# Kaya.net
KiCad netlist of a schematic drawn in EAGLE
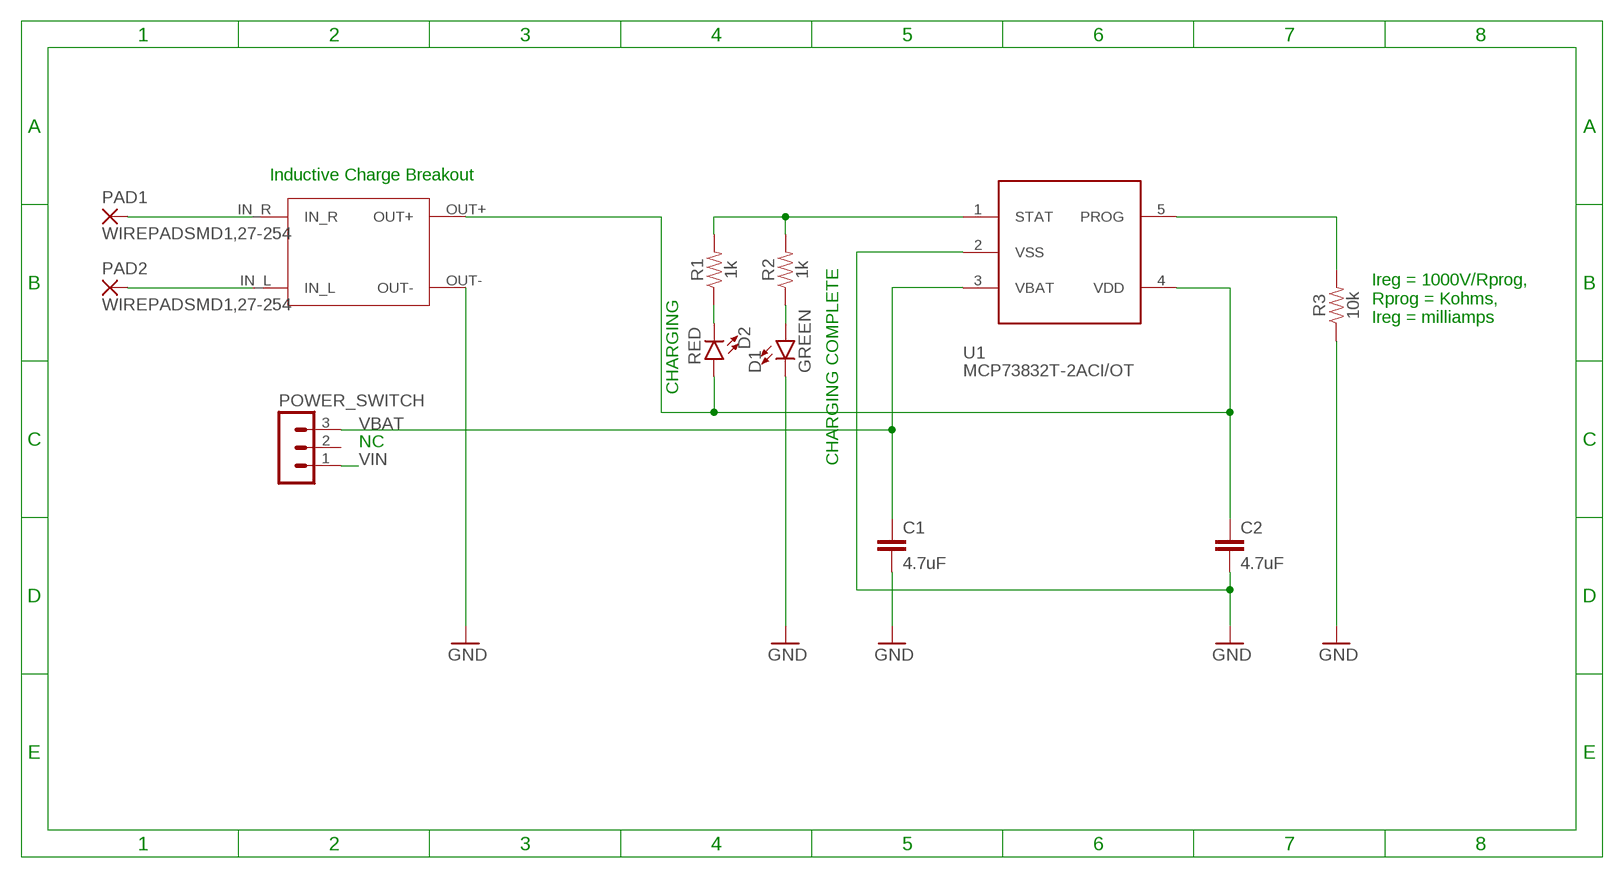
[diagram p0: schematic, sheet 1]
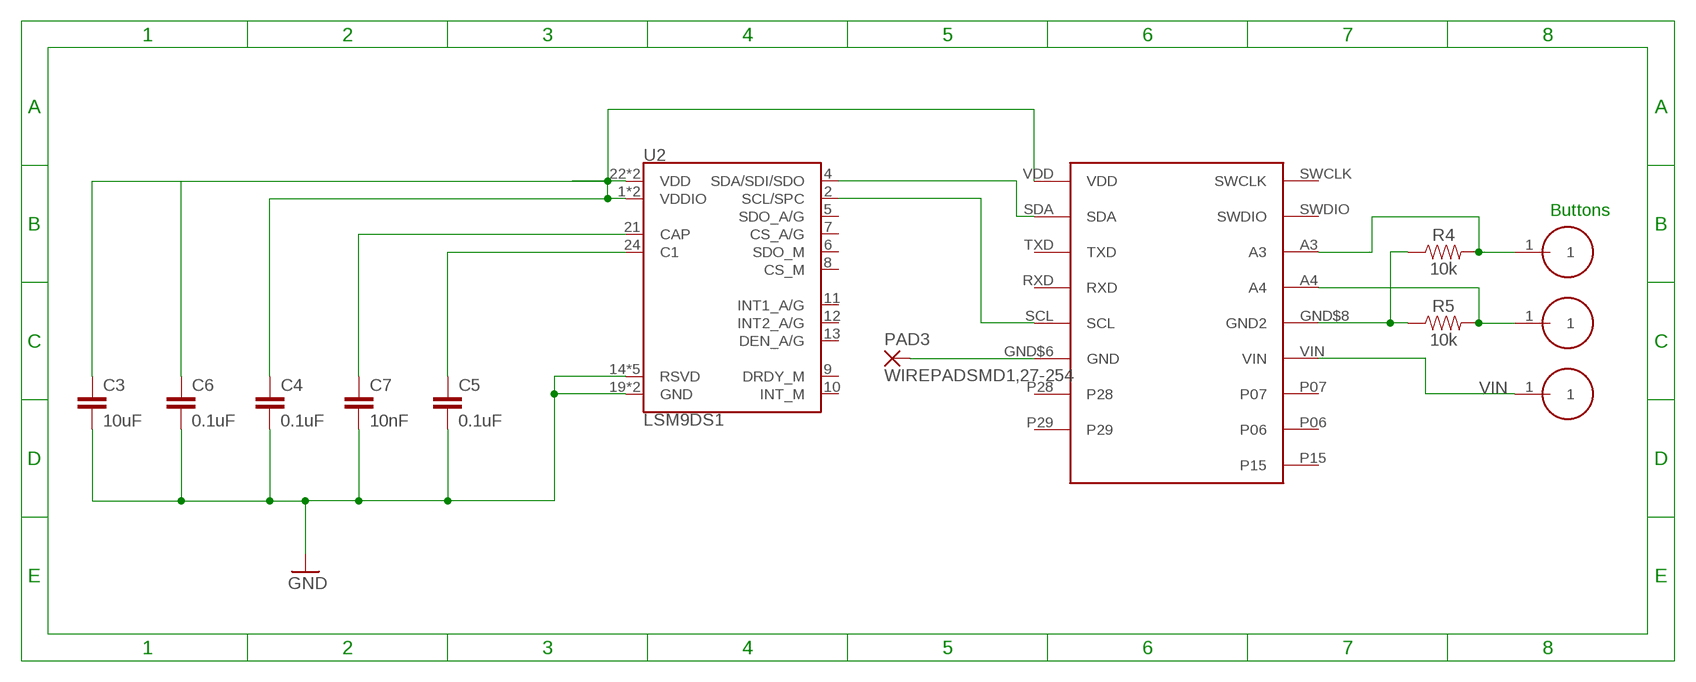
[diagram p1: schematic, sheet 2]

(export (version "E")
  (design (tool "Eeschema 10.0.6"))
  (components
    (comp (ref "C3")
      (value "10uF")
      (footprint "eagle-import:0603")
      (libsource (lib "eagle-import") (part "10UF-0603-6.3V-20%"))
    )
    (comp (ref "C4")
      (value "0.1uF")
      (footprint "eagle-import:0603")
      (libsource (lib "eagle-import") (part "0.1UF-0603-25V-(+80/-20%)"))
    )
    (comp (ref "C5")
      (value "0.1uF")
      (footprint "eagle-import:0603")
      (libsource (lib "eagle-import") (part "0.1UF-0603-25V-(+80/-20%)"))
    )
    (comp (ref "C6")
      (value "0.1uF")
      (footprint "eagle-import:0603")
      (libsource (lib "eagle-import") (part "0.1UF-0603-25V-(+80/-20%)"))
    )
    (comp (ref "C7")
      (value "10nF")
      (footprint "eagle-import:0603")
      (libsource (lib "eagle-import") (part "10NF-0603-50V-10%"))
    )
    (comp (ref "PAD3")
      (value "WIREPADSMD1,27-254")
      (footprint "eagle-import:SMD1,27-2,54")
      (libsource (lib "eagle-import") (part "WIREPADSMD1,27-254"))
    )
    (comp (ref "R4")
      (value "10k")
      (footprint "eagle-import:0603")
      (libsource (lib "eagle-import") (part "10KOHM-0603-1/10W-1%"))
    )
    (comp (ref "R5")
      (value "10k")
      (footprint "eagle-import:0603")
      (libsource (lib "eagle-import") (part "10KOHM-0603-1/10W-1%"))
    )
    (comp (ref "U$2")
      (value "BLE-NANO")
      (footprint "eagle-import:BLE-NANO-PKG")
      (libsource (lib "eagle-import") (part "BLE-NANO"))
    )
    (comp (ref "U$3")
      (value "CONDUCTIVE-BUTTON")
      (footprint "eagle-import:CONDUCTIVE-BUTTON")
      (libsource (lib "eagle-import") (part "CONDUCTIVE-BUTTON"))
    )
    (comp (ref "U$4")
      (value "CONDUCTIVE-BUTTON")
      (footprint "eagle-import:CONDUCTIVE-BUTTON")
      (libsource (lib "eagle-import") (part "CONDUCTIVE-BUTTON"))
    )
    (comp (ref "U$5")
      (value "CONDUCTIVE-BUTTON")
      (footprint "eagle-import:CONDUCTIVE-BUTTON")
      (libsource (lib "eagle-import") (part "CONDUCTIVE-BUTTON"))
    )
    (comp (ref "U2")
      (value "LSM9DS1")
      (footprint "eagle-import:LGA-24-3.5X3")
      (libsource (lib "eagle-import") (part "LSM9DS1"))
    )
    (comp (ref "C1")
      (value "4.7uF")
      (footprint "eagle-import:0603")
      (libsource (lib "eagle-import") (part "4.7UF0603"))
    )
    (comp (ref "C2")
      (value "4.7uF")
      (footprint "eagle-import:0603")
      (libsource (lib "eagle-import") (part "4.7UF0603"))
    )
    (comp (ref "D1")
      (value "GREEN")
      (footprint "eagle-import:LED-0603")
      (libsource (lib "eagle-import") (part "LED-GREEN0603"))
    )
    (comp (ref "D2")
      (value "RED")
      (footprint "eagle-import:LED-0603")
      (libsource (lib "eagle-import") (part "LED-RED0603"))
    )
    (comp (ref "PAD1")
      (value "WIREPADSMD1,27-254")
      (footprint "eagle-import:SMD1,27-2,54")
      (libsource (lib "eagle-import") (part "WIREPADSMD1,27-254"))
    )
    (comp (ref "PAD2")
      (value "WIREPADSMD1,27-254")
      (footprint "eagle-import:SMD1,27-2,54")
      (libsource (lib "eagle-import") (part "WIREPADSMD1,27-254"))
    )
    (comp (ref "POWER_SWITCH")
      (value "MA03-1")
      (footprint "eagle-import:MA03-1")
      (libsource (lib "eagle-import") (part "MA03-1"))
    )
    (comp (ref "R1")
      (value "1k")
      (footprint "eagle-import:0603")
      (libsource (lib "eagle-import") (part "1KOHM-0603-1/10W-1%"))
    )
    (comp (ref "R2")
      (value "1k")
      (footprint "eagle-import:0603")
      (libsource (lib "eagle-import") (part "1KOHM-0603-1/10W-1%"))
    )
    (comp (ref "R3")
      (value "10k")
      (footprint "eagle-import:0603")
      (libsource (lib "eagle-import") (part "10KOHM-0603-1/10W-1%"))
    )
    (comp (ref "U$1")
      (value "INDUCTIVE-CHARGE-5V")
      (footprint "eagle-import:INDUCTIVE-CHARGE-5V")
      (libsource (lib "eagle-import") (part "INDUCTIVE-CHARGE-5V"))
    )
    (comp (ref "U1")
      (value "MCP73832T-2ACI/OT")
      (footprint "eagle-import:SOT23-5")
      (fields (field (name "MF") "Microchip") (field (name "MP") "MCP73832T-2ACI-OT"))
      (libsource (lib "eagle-import") (part "MCP73832T-2ACI/OT"))
    )
  )
  (nets
    (net (code "1") (name "GND") (class "Default")
      (node (ref "C1") (pin "2") (pinfunction "2_2") (pintype "passive"))
      (node (ref "C2") (pin "2") (pinfunction "2_2") (pintype "passive"))
      (node (ref "C3") (pin "2") (pinfunction "2_2") (pintype "passive"))
      (node (ref "C4") (pin "2") (pinfunction "2_2") (pintype "passive"))
      (node (ref "C5") (pin "2") (pinfunction "2_2") (pintype "passive"))
      (node (ref "C6") (pin "2") (pinfunction "2_2") (pintype "passive"))
      (node (ref "C7") (pin "2") (pinfunction "2_2") (pintype "passive"))
      (node (ref "D1") (pin "C") (pinfunction "C_C") (pintype "passive"))
      (node (ref "R3") (pin "1") (pinfunction "1_1") (pintype "passive"))
      (node (ref "U$1") (pin "OUT-") (pinfunction "OUT-_OUT-") (pintype "bidirectional"))
      (node (ref "U1") (pin "2") (pinfunction "VSS_2") (pintype "passive"))
      (node (ref "U2") (pin "14") (pinfunction "RSVD_14") (pintype "bidirectional"))
      (node (ref "U2") (pin "15") (pinfunction "RSVD_15") (pintype "bidirectional"))
      (node (ref "U2") (pin "16") (pinfunction "RSVD_16") (pintype "bidirectional"))
      (node (ref "U2") (pin "17") (pinfunction "RSVD_17") (pintype "bidirectional"))
      (node (ref "U2") (pin "18") (pinfunction "RSVD_18") (pintype "bidirectional"))
      (node (ref "U2") (pin "19") (pinfunction "GND_19") (pintype "bidirectional"))
      (node (ref "U2") (pin "20") (pinfunction "GND_20") (pintype "bidirectional"))
    )
    (net (code "2") (name "Net-(C3-Pad1)") (class "Default")
      (node (ref "C3") (pin "1") (pinfunction "1_1") (pintype "passive"))
      (node (ref "C4") (pin "1") (pinfunction "1_1") (pintype "passive"))
      (node (ref "C6") (pin "1") (pinfunction "1_1") (pintype "passive"))
      (node (ref "U$2") (pin "VDD") (pinfunction "VDD_VDD") (pintype "bidirectional"))
      (node (ref "U2") (pin "1") (pinfunction "VDDIO_1") (pintype "bidirectional"))
      (node (ref "U2") (pin "22") (pinfunction "VDD_22") (pintype "bidirectional"))
      (node (ref "U2") (pin "23") (pinfunction "VDD_23") (pintype "bidirectional"))
      (node (ref "U2") (pin "3") (pinfunction "VDDIO_3") (pintype "bidirectional"))
    )
    (net (code "3") (name "Net-(D1-PadA)") (class "Default")
      (node (ref "D1") (pin "A") (pinfunction "A_A") (pintype "passive"))
      (node (ref "R2") (pin "1") (pinfunction "1_1") (pintype "passive"))
    )
    (net (code "4") (name "Net-(D2-PadC)") (class "Default")
      (node (ref "D2") (pin "C") (pinfunction "C_C") (pintype "passive"))
      (node (ref "R1") (pin "1") (pinfunction "1_1") (pintype "passive"))
    )
    (net (code "5") (name "Net-(PAD1-P)") (class "Default")
      (node (ref "PAD1") (pin "1") (pinfunction "P_1") (pintype "passive"))
      (node (ref "U$1") (pin "IN_R") (pinfunction "IN_R_IN_R") (pintype "bidirectional"))
    )
    (net (code "6") (name "Net-(PAD2-P)") (class "Default")
      (node (ref "PAD2") (pin "1") (pinfunction "P_1") (pintype "passive"))
      (node (ref "U$1") (pin "IN_L") (pinfunction "IN_L_IN_L") (pintype "bidirectional"))
    )
    (net (code "7") (name "Net-(PAD3-P)") (class "Default")
      (node (ref "PAD3") (pin "1") (pinfunction "P_1") (pintype "passive"))
      (node (ref "U$2") (pin "GND$6") (pinfunction "GND_GND$6") (pintype "bidirectional"))
    )
    (net (code "8") (name "Net-(R4-Pad2)") (class "Default")
      (node (ref "R4") (pin "2") (pinfunction "2_2") (pintype "passive"))
      (node (ref "U$2") (pin "A3") (pinfunction "A3_A3") (pintype "bidirectional"))
      (node (ref "U$3") (pin "1") (pinfunction "1_1") (pintype "bidirectional"))
    )
    (net (code "9") (name "Net-(R5-Pad2)") (class "Default")
      (node (ref "R5") (pin "2") (pinfunction "2_2") (pintype "passive"))
      (node (ref "U$2") (pin "A4") (pinfunction "A4_A4") (pintype "bidirectional"))
      (node (ref "U$4") (pin "1") (pinfunction "1_1") (pintype "bidirectional"))
    )
    (net (code "10") (name "Net-(U$2-GND2)") (class "Default")
      (node (ref "R4") (pin "1") (pinfunction "1_1") (pintype "passive"))
      (node (ref "R5") (pin "1") (pinfunction "1_1") (pintype "passive"))
      (node (ref "U$2") (pin "GND$8") (pinfunction "GND2_GND$8") (pintype "bidirectional"))
    )
    (net (code "11") (name "Net-(U1-PROG)") (class "Default")
      (node (ref "R3") (pin "2") (pinfunction "2_2") (pintype "passive"))
      (node (ref "U1") (pin "5") (pinfunction "PROG_5") (pintype "input"))
    )
    (net (code "12") (name "Net-(U1-STAT)") (class "Default")
      (node (ref "R1") (pin "2") (pinfunction "2_2") (pintype "passive"))
      (node (ref "R2") (pin "2") (pinfunction "2_2") (pintype "passive"))
      (node (ref "U1") (pin "1") (pinfunction "STAT_1") (pintype "output"))
    )
    (net (code "13") (name "Net-(U1-VDD)") (class "Default")
      (node (ref "C2") (pin "1") (pinfunction "1_1") (pintype "passive"))
      (node (ref "D2") (pin "A") (pinfunction "A_A") (pintype "passive"))
      (node (ref "U$1") (pin "OUT+") (pinfunction "OUT+_OUT+") (pintype "bidirectional"))
      (node (ref "U1") (pin "4") (pinfunction "VDD_4") (pintype "input"))
    )
    (net (code "14") (name "Net-(U2-C1)") (class "Default")
      (node (ref "C5") (pin "1") (pinfunction "1_1") (pintype "passive"))
      (node (ref "U2") (pin "24") (pinfunction "C1_24") (pintype "bidirectional"))
    )
    (net (code "15") (name "Net-(U2-CAP)") (class "Default")
      (node (ref "C7") (pin "1") (pinfunction "1_1") (pintype "passive"))
      (node (ref "U2") (pin "21") (pinfunction "CAP_21") (pintype "bidirectional"))
    )
    (net (code "16") (name "Net-(U2-SCL{slash}SPC)") (class "Default")
      (node (ref "U$2") (pin "SCL") (pinfunction "SCL_SCL") (pintype "bidirectional"))
      (node (ref "U2") (pin "2") (pinfunction "SCL/SPC_2") (pintype "bidirectional"))
    )
    (net (code "17") (name "Net-(U2-SDA{slash}SDI{slash}SDO)") (class "Default")
      (node (ref "U$2") (pin "SDA") (pinfunction "SDA_SDA") (pintype "bidirectional"))
      (node (ref "U2") (pin "4") (pinfunction "SDA/SDI/SDO_4") (pintype "bidirectional"))
    )
    (net (code "18") (name "VBAT") (class "Default")
      (node (ref "C1") (pin "1") (pinfunction "1_1") (pintype "passive"))
      (node (ref "POWER_SWITCH") (pin "3") (pinfunction "3_3") (pintype "passive"))
      (node (ref "U1") (pin "3") (pinfunction "VBAT_3") (pintype "output"))
    )
    (net (code "19") (name "VIN") (class "Default")
      (node (ref "POWER_SWITCH") (pin "1") (pinfunction "1_1") (pintype "passive"))
      (node (ref "U$2") (pin "VIN") (pinfunction "VIN_VIN") (pintype "bidirectional"))
      (node (ref "U$5") (pin "1") (pinfunction "1_1") (pintype "bidirectional"))
    )
    (net (code "20") (name "unconnected-(POWER_SWITCH-Pad2)") (class "Default")
      (node (ref "POWER_SWITCH") (pin "2") (pinfunction "2_2") (pintype "passive"))
    )
    (net (code "21") (name "unconnected-(U$2-PadP06)") (class "Default")
      (node (ref "U$2") (pin "P06") (pinfunction "P06_P06") (pintype "bidirectional"))
    )
    (net (code "22") (name "unconnected-(U$2-PadP07)") (class "Default")
      (node (ref "U$2") (pin "P07") (pinfunction "P07_P07") (pintype "bidirectional"))
    )
    (net (code "23") (name "unconnected-(U$2-PadP15)") (class "Default")
      (node (ref "U$2") (pin "P15") (pinfunction "P15_P15") (pintype "bidirectional"))
    )
    (net (code "24") (name "unconnected-(U$2-PadP28)") (class "Default")
      (node (ref "U$2") (pin "P28") (pinfunction "P28_P28") (pintype "bidirectional"))
    )
    (net (code "25") (name "unconnected-(U$2-PadP29)") (class "Default")
      (node (ref "U$2") (pin "P29") (pinfunction "P29_P29") (pintype "bidirectional"))
    )
    (net (code "26") (name "unconnected-(U$2-PadRXD)") (class "Default")
      (node (ref "U$2") (pin "RXD") (pinfunction "RXD_RXD") (pintype "bidirectional"))
    )
    (net (code "27") (name "unconnected-(U$2-PadSWCLK)") (class "Default")
      (node (ref "U$2") (pin "SWCLK") (pinfunction "SWCLK_SWCLK") (pintype "bidirectional"))
    )
    (net (code "28") (name "unconnected-(U$2-PadSWDIO)") (class "Default")
      (node (ref "U$2") (pin "SWDIO") (pinfunction "SWDIO_SWDIO") (pintype "bidirectional"))
    )
    (net (code "29") (name "unconnected-(U$2-PadTXD)") (class "Default")
      (node (ref "U$2") (pin "TXD") (pinfunction "TXD_TXD") (pintype "bidirectional"))
    )
    (net (code "30") (name "unconnected-(U2-CS_A{slash}G-Pad7)") (class "Default")
      (node (ref "U2") (pin "7") (pinfunction "CS_A/G_7") (pintype "bidirectional"))
    )
    (net (code "31") (name "unconnected-(U2-CS_M-Pad8)") (class "Default")
      (node (ref "U2") (pin "8") (pinfunction "CS_M_8") (pintype "bidirectional"))
    )
    (net (code "32") (name "unconnected-(U2-DEN_A{slash}G-Pad13)") (class "Default")
      (node (ref "U2") (pin "13") (pinfunction "DEN_A/G_13") (pintype "bidirectional"))
    )
    (net (code "33") (name "unconnected-(U2-DRDY_M-Pad9)") (class "Default")
      (node (ref "U2") (pin "9") (pinfunction "DRDY_M_9") (pintype "bidirectional"))
    )
    (net (code "34") (name "unconnected-(U2-INT1_A{slash}G-Pad11)") (class "Default")
      (node (ref "U2") (pin "11") (pinfunction "INT1_A/G_11") (pintype "bidirectional"))
    )
    (net (code "35") (name "unconnected-(U2-INT2_A{slash}G-Pad12)") (class "Default")
      (node (ref "U2") (pin "12") (pinfunction "INT2_A/G_12") (pintype "bidirectional"))
    )
    (net (code "36") (name "unconnected-(U2-INT_M-Pad10)") (class "Default")
      (node (ref "U2") (pin "10") (pinfunction "INT_M_10") (pintype "bidirectional"))
    )
    (net (code "37") (name "unconnected-(U2-SDO_A{slash}G-Pad5)") (class "Default")
      (node (ref "U2") (pin "5") (pinfunction "SDO_A/G_5") (pintype "bidirectional"))
    )
    (net (code "38") (name "unconnected-(U2-SDO_M-Pad6)") (class "Default")
      (node (ref "U2") (pin "6") (pinfunction "SDO_M_6") (pintype "bidirectional"))
    )
  )
)
